# USB-to-UART.net
KiCad netlist of a schematic drawn in Altium Designer
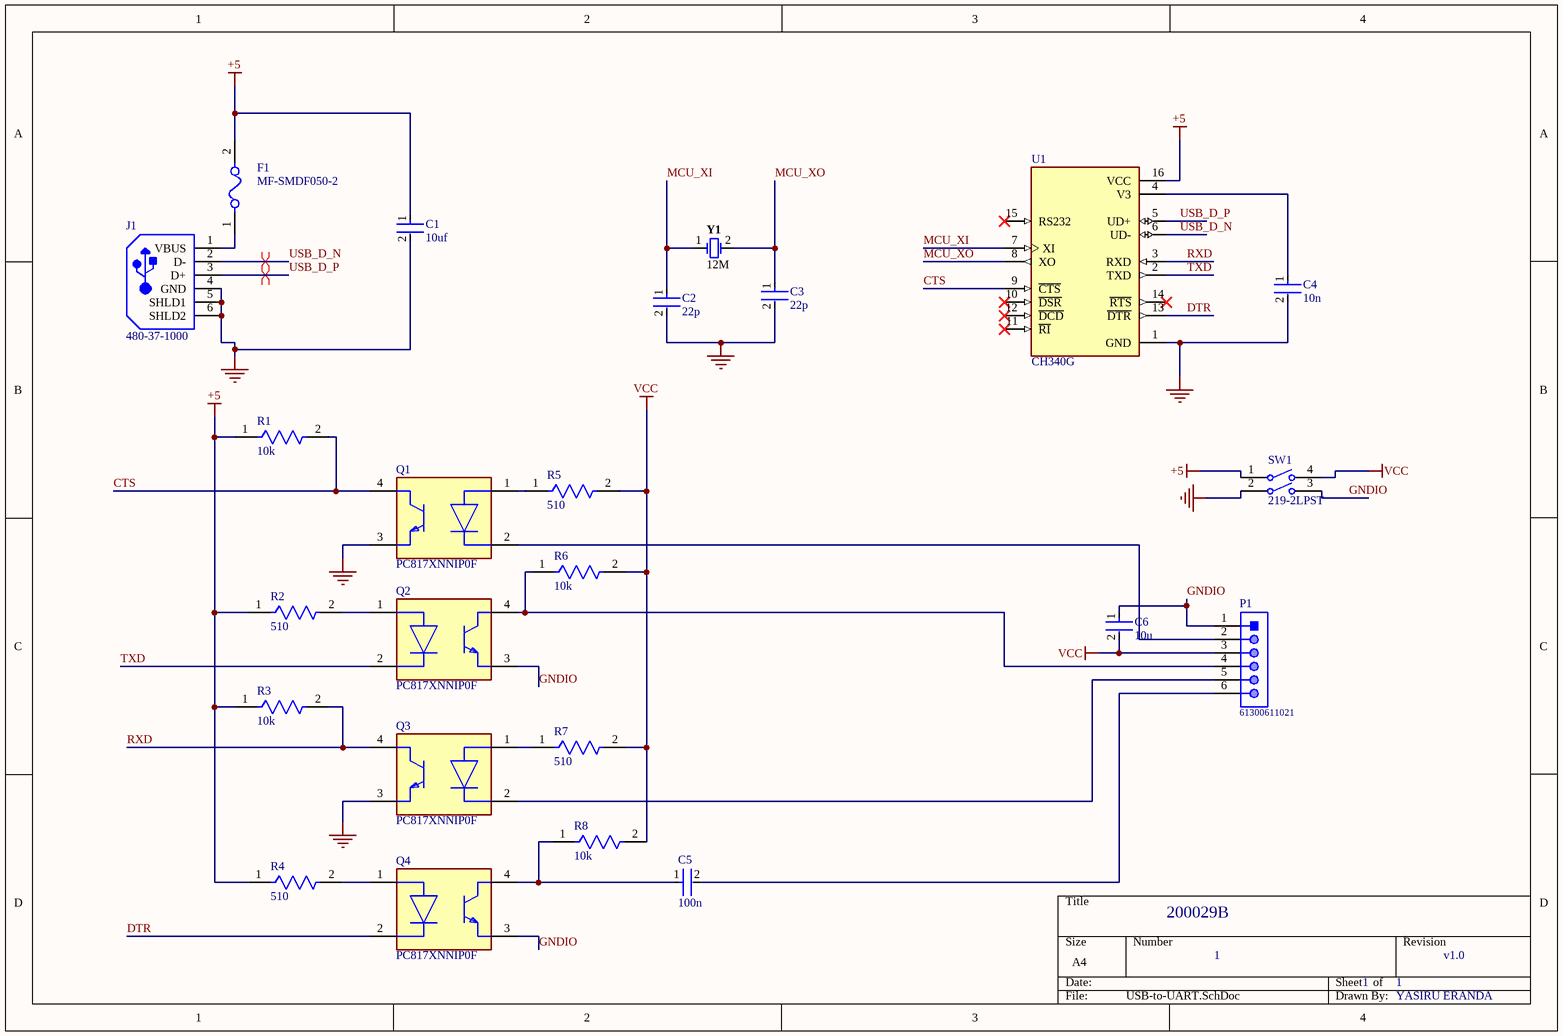
[diagram p0: USB-to-UART.SchDoc]

(export (version "E")
  (design (tool "Eeschema 10.0.6"))
  (components
    (comp (ref "C1")
      (value "10uf")
      (footprint "FP-0805P-MFG")
      (description "CAP CER 10UF 25V X5R 0805")
      (fields (field (name "TOLERANCE") "10%"))
      (libsource (lib "Altium Content Vault") (part "11868f565c42a9108669ba33697ecf6"))
    )
    (comp (ref "C2")
      (value "22p")
      (footprint "FP-0603-L_1_6_0_15-W_0_81-IPC_C")
      (description "General Purpose Ceramic Capacitor, 0603, 22pF, 5%, NP0, 30ppm/°C, 50V")
      (fields (field (name "VOLTAGE") "50V") (field (name "TOLERANCE") "5%"))
      (libsource (lib "Altium Content Vault") (part "02cd4be3c70576c341d710602a673aa"))
    )
    (comp (ref "C3")
      (value "22p")
      (footprint "FP-0603-L_1_6_0_15-W_0_81-IPC_C")
      (description "General Purpose Ceramic Capacitor, 0603, 22pF, 5%, NP0, 30ppm/°C, 50V")
      (fields (field (name "VOLTAGE") "50V") (field (name "TOLERANCE") "5%"))
      (libsource (lib "Altium Content Vault") (part "02cd4be3c70576c341d710602a673aa"))
    )
    (comp (ref "C4")
      (value "10n")
      (footprint "FP-0603-L_1_6_0_15-W_0_81-IPC_C")
      (description "General Purpose Ceramic Capacitor, 0603, 22pF, 5%, NP0, 30ppm/°C, 50V")
      (fields (field (name "VOLTAGE") "50V") (field (name "TOLERANCE") "5%"))
      (libsource (lib "Altium Content Vault") (part "02cd4be3c70576c341d710602a673aa"))
    )
    (comp (ref "C5")
      (value "100n")
      (footprint "FP-0603-L_1_6_0_15-W_0_81-IPC_C")
      (description "General Purpose Ceramic Capacitor, 0603, 22pF, 5%, NP0, 30ppm/°C, 50V")
      (fields (field (name "VOLTAGE") "50V") (field (name "TOLERANCE") "5%"))
      (libsource (lib "Altium Content Vault") (part "02cd4be3c70576c341d710602a673aa"))
    )
    (comp (ref "C6")
      (value "10u")
      (footprint "FP-0805P-MFG")
      (description "CAP CER 10UF 25V X5R 0805")
      (fields (field (name "TOLERANCE") "10%"))
      (libsource (lib "Altium Content Vault") (part "11868f565c42a9108669ba33697ecf6"))
    )
    (comp (ref "F1")
      (value "MF-SMDF050-2")
      (footprint "FP-MF-SMDF-MFG")
      (description "PTC RESET FUSE 60V 550MA 2018")
      (fields
        (field (name "OCTOPART") "https://octopart.com/mf-smdf050-2-bourns-94955")
        (field (name "MANUFACTURER") "Bourns Inc.")
      )
      (libsource (lib "Altium Content Vault") (part "5bcf9b9f640e542cf0359d10258e979"))
    )
    (comp (ref "J1")
      (value "480-37-1000")
      (footprint "MOLX-480-37-1000_V")
      (fields (field (name "TOLERANCE") "1%"))
      (libsource (lib "Altium Content Vault") (part "USB-4-2SHLD"))
    )
    (comp (ref "P1")
      (value "61300611021")
      (footprint "61300611021")
      (description "THT Angled Pin Header WR-PHD, Pitch 2.54 mm, Single Row, 6 pins")
      (fields (field (name "MANUFACTURER") "Wurth Elektronik") (field (name "PUBLISHER") "WurthElektronik"))
      (libsource (lib "Altium Content Vault") (part "WE-CN-1P-M-R6"))
    )
    (comp (ref "Q1")
      (value "PC817XNNIP0F")
      (footprint "FP-PC817XNNIP0F-MFG")
      (description "OPTOISOLATOR 5KV TRANS 4SMD")
      (libsource (lib "Altium Content Vault") (part "6470904bf6395c62928ee73e60120b8"))
    )
    (comp (ref "Q2")
      (value "PC817XNNIP0F")
      (footprint "FP-PC817XNNIP0F-MFG")
      (description "OPTOISOLATOR 5KV TRANS 4SMD")
      (libsource (lib "") (part "6470904bf6395c62928ee73e60120b8_1"))
    )
    (comp (ref "Q3")
      (value "PC817XNNIP0F")
      (footprint "FP-PC817XNNIP0F-MFG")
      (description "OPTOISOLATOR 5KV TRANS 4SMD")
      (libsource (lib "Altium Content Vault") (part "6470904bf6395c62928ee73e60120b8"))
    )
    (comp (ref "Q4")
      (value "PC817XNNIP0F")
      (footprint "FP-PC817XNNIP0F-MFG")
      (description "OPTOISOLATOR 5KV TRANS 4SMD")
      (libsource (lib "") (part "6470904bf6395c62928ee73e60120b8_1"))
    )
    (comp (ref "R1")
      (value "10k")
      (footprint "FP-CRGP0603-IPC_C")
      (description "CRGP 0603 10K 1%")
      (fields
        (field (name "OCTOPART") "https://octopart.com/crgp0603f10k-te+connectivity-91018721")
        (field (name "MANUFACTURER PART NUMBER") "CRGP0603F10K")
      )
      (libsource (lib "Altium Content Vault") (part "1029c3af85768c4190bb7ad29bc67b5"))
    )
    (comp (ref "R2")
      (value "510")
      (footprint "FP-CR0603-IPC_A")
      (description "Thick Film Chip Resistors 0603 510Ω 0.1W 1% 100ppm/°C")
      (fields (field (name "TOLERANCE") "1%"))
      (libsource (lib "Altium Content Vault") (part "1029c3af85768c4190bb7ad29bc67b5"))
    )
    (comp (ref "R3")
      (value "10k")
      (footprint "FP-CRGP0603-IPC_C")
      (description "CRGP 0603 10K 1%")
      (fields
        (field (name "OCTOPART") "https://octopart.com/crgp0603f10k-te+connectivity-91018721")
        (field (name "MANUFACTURER PART NUMBER") "CRGP0603F10K")
      )
      (libsource (lib "Altium Content Vault") (part "1029c3af85768c4190bb7ad29bc67b5"))
    )
    (comp (ref "R4")
      (value "510")
      (footprint "FP-CR0603-IPC_A")
      (description "Thick Film Chip Resistors 0603 510Ω 0.1W 1% 100ppm/°C")
      (fields (field (name "TOLERANCE") "1%"))
      (libsource (lib "Altium Content Vault") (part "1029c3af85768c4190bb7ad29bc67b5"))
    )
    (comp (ref "R5")
      (value "510")
      (footprint "FP-CR0603-IPC_A")
      (description "Thick Film Chip Resistors 0603 510Ω 0.1W 1% 100ppm/°C")
      (fields (field (name "TOLERANCE") "1%"))
      (libsource (lib "Altium Content Vault") (part "1029c3af85768c4190bb7ad29bc67b5"))
    )
    (comp (ref "R6")
      (value "10k")
      (footprint "FP-CRGP0603-IPC_C")
      (description "CRGP 0603 10K 1%")
      (fields
        (field (name "OCTOPART") "https://octopart.com/crgp0603f10k-te+connectivity-91018721")
        (field (name "MANUFACTURER PART NUMBER") "CRGP0603F10K")
      )
      (libsource (lib "Altium Content Vault") (part "1029c3af85768c4190bb7ad29bc67b5"))
    )
    (comp (ref "R7")
      (value "510")
      (footprint "FP-CR0603-IPC_A")
      (description "Thick Film Chip Resistors 0603 510Ω 0.1W 1% 100ppm/°C")
      (fields (field (name "TOLERANCE") "1%"))
      (libsource (lib "Altium Content Vault") (part "1029c3af85768c4190bb7ad29bc67b5"))
    )
    (comp (ref "R8")
      (value "10k")
      (footprint "FP-CRGP0603-IPC_C")
      (description "CRGP 0603 10K 1%")
      (fields
        (field (name "OCTOPART") "https://octopart.com/crgp0603f10k-te+connectivity-91018721")
        (field (name "MANUFACTURER PART NUMBER") "CRGP0603F10K")
      )
      (libsource (lib "Altium Content Vault") (part "1029c3af85768c4190bb7ad29bc67b5"))
    )
    (comp (ref "SW1")
      (value "219-2LPST")
      (footprint "CTS-219-2LPST_V")
      (description "Surface Mount DIP Switch Auto Placeable, -55 to 85 degC, 4-Pin SMD, RoHS, Tube")
      (fields (field (name "MANUFACTURER") "CTS Corporation"))
      (libsource (lib "Altium Content Vault") (part "SW-SPST-4_C"))
    )
    (comp (ref "U1")
      (value "CH340G")
      (footprint "SOIC127P600X180-16N")
      (description "USB Interface Integrated Circuit")
      (fields (field (name "MP") "Ch340G") (field (name "MF") "WCH"))
      (libsource (lib "CH340G") (part "CH340G"))
    )
    (comp (ref "Y1")
      (value "12M")
      (footprint "FOX-FOXSLF-2_V")
      (description "Resistance Weld Thru-Hole Crystal, 12 MHz, +/-30 ppm, -20 to 70 degC, 2-Pin THD, RoHS, Bulk")
      (libsource (lib "Altium Content Vault") (part "XTAL-1-2-2"))
    )
  )
  (nets
    (net (code "1") (name "+5") (class "Default")
      (node (ref "C1") (pin "1") (pinfunction "1_1") (pintype "passive"))
      (node (ref "F1") (pin "2") (pinfunction "2_2") (pintype "passive"))
      (node (ref "R1") (pin "1") (pinfunction "1_1") (pintype "passive"))
      (node (ref "R2") (pin "1") (pinfunction "1_1") (pintype "passive"))
      (node (ref "R3") (pin "1") (pinfunction "1_1") (pintype "passive"))
      (node (ref "R4") (pin "1") (pinfunction "1_1") (pintype "passive"))
      (node (ref "SW1") (pin "1") (pinfunction "1_1") (pintype "passive"))
      (node (ref "U1") (pin "16") (pinfunction "VCC_16") (pintype "power_in"))
    )
    (net (code "2") (name "/CTS") (class "Default")
      (node (ref "Q1") (pin "4") (pinfunction "C_4") (pintype "passive"))
      (node (ref "R1") (pin "2") (pinfunction "2_2") (pintype "passive"))
      (node (ref "U1") (pin "9") (pinfunction "~{CTS}_9") (pintype "input"))
    )
    (net (code "3") (name "/DTR") (class "Default")
      (node (ref "Q4") (pin "2") (pinfunction "C_2") (pintype "passive"))
      (node (ref "U1") (pin "13") (pinfunction "~{DTR}_13") (pintype "output"))
    )
    (net (code "4") (name "/GNDIO") (class "Default")
      (node (ref "C6") (pin "1") (pinfunction "1_1") (pintype "passive"))
      (node (ref "P1") (pin "1") (pinfunction "1_1") (pintype "passive"))
      (node (ref "Q2") (pin "3") (pinfunction "E_3") (pintype "passive"))
      (node (ref "Q4") (pin "3") (pinfunction "E_3") (pintype "passive"))
      (node (ref "SW1") (pin "3") (pinfunction "3_3") (pintype "passive"))
    )
    (net (code "5") (name "/MCU_XI") (class "Default")
      (node (ref "C2") (pin "1") (pinfunction "1_1") (pintype "passive"))
      (node (ref "U1") (pin "7") (pinfunction "XI_7") (pintype "input"))
      (node (ref "Y1") (pin "1") (pinfunction "1_1") (pintype "passive"))
    )
    (net (code "6") (name "/MCU_XO") (class "Default")
      (node (ref "C3") (pin "1") (pinfunction "1_1") (pintype "passive"))
      (node (ref "U1") (pin "8") (pinfunction "XO_8") (pintype "output"))
      (node (ref "Y1") (pin "2") (pinfunction "2_2") (pintype "passive"))
    )
    (net (code "7") (name "/RXD") (class "Default")
      (node (ref "Q3") (pin "4") (pinfunction "C_4") (pintype "passive"))
      (node (ref "R3") (pin "2") (pinfunction "2_2") (pintype "passive"))
      (node (ref "U1") (pin "3") (pinfunction "RXD_3") (pintype "input"))
    )
    (net (code "8") (name "/TXD") (class "Default")
      (node (ref "Q2") (pin "2") (pinfunction "C_2") (pintype "passive"))
      (node (ref "U1") (pin "2") (pinfunction "TXD_2") (pintype "output"))
    )
    (net (code "9") (name "/USB_D_N") (class "Default")
      (node (ref "J1") (pin "2") (pinfunction "D-_2") (pintype "passive"))
      (node (ref "U1") (pin "6") (pinfunction "UD-_6") (pintype "bidirectional"))
    )
    (net (code "10") (name "/USB_D_P") (class "Default")
      (node (ref "J1") (pin "3") (pinfunction "D+_3") (pintype "passive"))
      (node (ref "U1") (pin "5") (pinfunction "UD+_5") (pintype "bidirectional"))
    )
    (net (code "11") (name "GND") (class "Default")
      (node (ref "C1") (pin "2") (pinfunction "2_2") (pintype "passive"))
      (node (ref "C2") (pin "2") (pinfunction "2_2") (pintype "passive"))
      (node (ref "C3") (pin "2") (pinfunction "2_2") (pintype "passive"))
      (node (ref "C4") (pin "2") (pinfunction "2_2") (pintype "passive"))
      (node (ref "J1") (pin "4") (pinfunction "GND_4") (pintype "passive"))
      (node (ref "J1") (pin "5") (pinfunction "SHLD1_5") (pintype "passive"))
      (node (ref "J1") (pin "6") (pinfunction "SHLD2_6") (pintype "passive"))
      (node (ref "Q1") (pin "3") (pinfunction "E_3") (pintype "passive"))
      (node (ref "Q3") (pin "3") (pinfunction "E_3") (pintype "passive"))
      (node (ref "SW1") (pin "2") (pinfunction "2_2") (pintype "passive"))
      (node (ref "U1") (pin "1") (pinfunction "GND_1") (pintype "power_in"))
    )
    (net (code "12") (name "Net-(C5-Pad1)") (class "Default")
      (node (ref "C5") (pin "1") (pinfunction "1_1") (pintype "passive"))
      (node (ref "Q4") (pin "4") (pinfunction "C_4") (pintype "passive"))
      (node (ref "R8") (pin "1") (pinfunction "1_1") (pintype "passive"))
    )
    (net (code "13") (name "Net-(C5-Pad2)") (class "Default")
      (node (ref "C5") (pin "2") (pinfunction "2_2") (pintype "passive"))
      (node (ref "P1") (pin "6") (pinfunction "6_6") (pintype "passive"))
    )
    (net (code "14") (name "Net-(J1-VBUS)") (class "Default")
      (node (ref "F1") (pin "1") (pinfunction "1_1") (pintype "passive"))
      (node (ref "J1") (pin "1") (pinfunction "VBUS_1") (pintype "passive"))
    )
    (net (code "15") (name "Net-(P1-Pad2)") (class "Default")
      (node (ref "P1") (pin "2") (pinfunction "2_2") (pintype "passive"))
      (node (ref "Q1") (pin "2") (pinfunction "C_2") (pintype "passive"))
    )
    (net (code "16") (name "Net-(P1-Pad4)") (class "Default")
      (node (ref "P1") (pin "4") (pinfunction "4_4") (pintype "passive"))
      (node (ref "Q2") (pin "4") (pinfunction "C_4") (pintype "passive"))
      (node (ref "R6") (pin "1") (pinfunction "1_1") (pintype "passive"))
    )
    (net (code "17") (name "Net-(P1-Pad5)") (class "Default")
      (node (ref "P1") (pin "5") (pinfunction "5_5") (pintype "passive"))
      (node (ref "Q3") (pin "2") (pinfunction "C_2") (pintype "passive"))
    )
    (net (code "18") (name "Net-(Q1-A)") (class "Default")
      (node (ref "Q1") (pin "1") (pinfunction "A_1") (pintype "passive"))
      (node (ref "R5") (pin "1") (pinfunction "1_1") (pintype "passive"))
    )
    (net (code "19") (name "Net-(Q2-A)") (class "Default")
      (node (ref "Q2") (pin "1") (pinfunction "A_1") (pintype "passive"))
      (node (ref "R2") (pin "2") (pinfunction "2_2") (pintype "passive"))
    )
    (net (code "20") (name "Net-(Q3-A)") (class "Default")
      (node (ref "Q3") (pin "1") (pinfunction "A_1") (pintype "passive"))
      (node (ref "R7") (pin "1") (pinfunction "1_1") (pintype "passive"))
    )
    (net (code "21") (name "Net-(Q4-A)") (class "Default")
      (node (ref "Q4") (pin "1") (pinfunction "A_1") (pintype "passive"))
      (node (ref "R4") (pin "2") (pinfunction "2_2") (pintype "passive"))
    )
    (net (code "22") (name "Net-(U1-V3)") (class "Default")
      (node (ref "C4") (pin "1") (pinfunction "1_1") (pintype "passive"))
      (node (ref "U1") (pin "4") (pinfunction "V3_4") (pintype "power_in"))
    )
    (net (code "23") (name "VCC") (class "Default")
      (node (ref "C6") (pin "2") (pinfunction "2_2") (pintype "passive"))
      (node (ref "P1") (pin "3") (pinfunction "3_3") (pintype "passive"))
      (node (ref "R5") (pin "2") (pinfunction "2_2") (pintype "passive"))
      (node (ref "R6") (pin "2") (pinfunction "2_2") (pintype "passive"))
      (node (ref "R7") (pin "2") (pinfunction "2_2") (pintype "passive"))
      (node (ref "R8") (pin "2") (pinfunction "2_2") (pintype "passive"))
      (node (ref "SW1") (pin "4") (pinfunction "4_4") (pintype "passive"))
    )
    (net (code "24") (name "unconnected-(U1-RS232-Pad15)") (class "Default")
      (node (ref "U1") (pin "15") (pinfunction "RS232_15") (pintype "input+no_connect"))
    )
    (net (code "25") (name "unconnected-(U1-~{DCD}-Pad12)") (class "Default")
      (node (ref "U1") (pin "12") (pinfunction "~{DCD}_12") (pintype "input+no_connect"))
    )
    (net (code "26") (name "unconnected-(U1-~{DSR}-Pad10)") (class "Default")
      (node (ref "U1") (pin "10") (pinfunction "~{DSR}_10") (pintype "input+no_connect"))
    )
    (net (code "27") (name "unconnected-(U1-~{RI}-Pad11)") (class "Default")
      (node (ref "U1") (pin "11") (pinfunction "~{RI}_11") (pintype "input+no_connect"))
    )
    (net (code "28") (name "unconnected-(U1-~{RTS}-Pad14)") (class "Default")
      (node (ref "U1") (pin "14") (pinfunction "~{RTS}_14") (pintype "output+no_connect"))
    )
  )
)
